# ULA.net
KiCad netlist of a schematic drawn in EAGLE
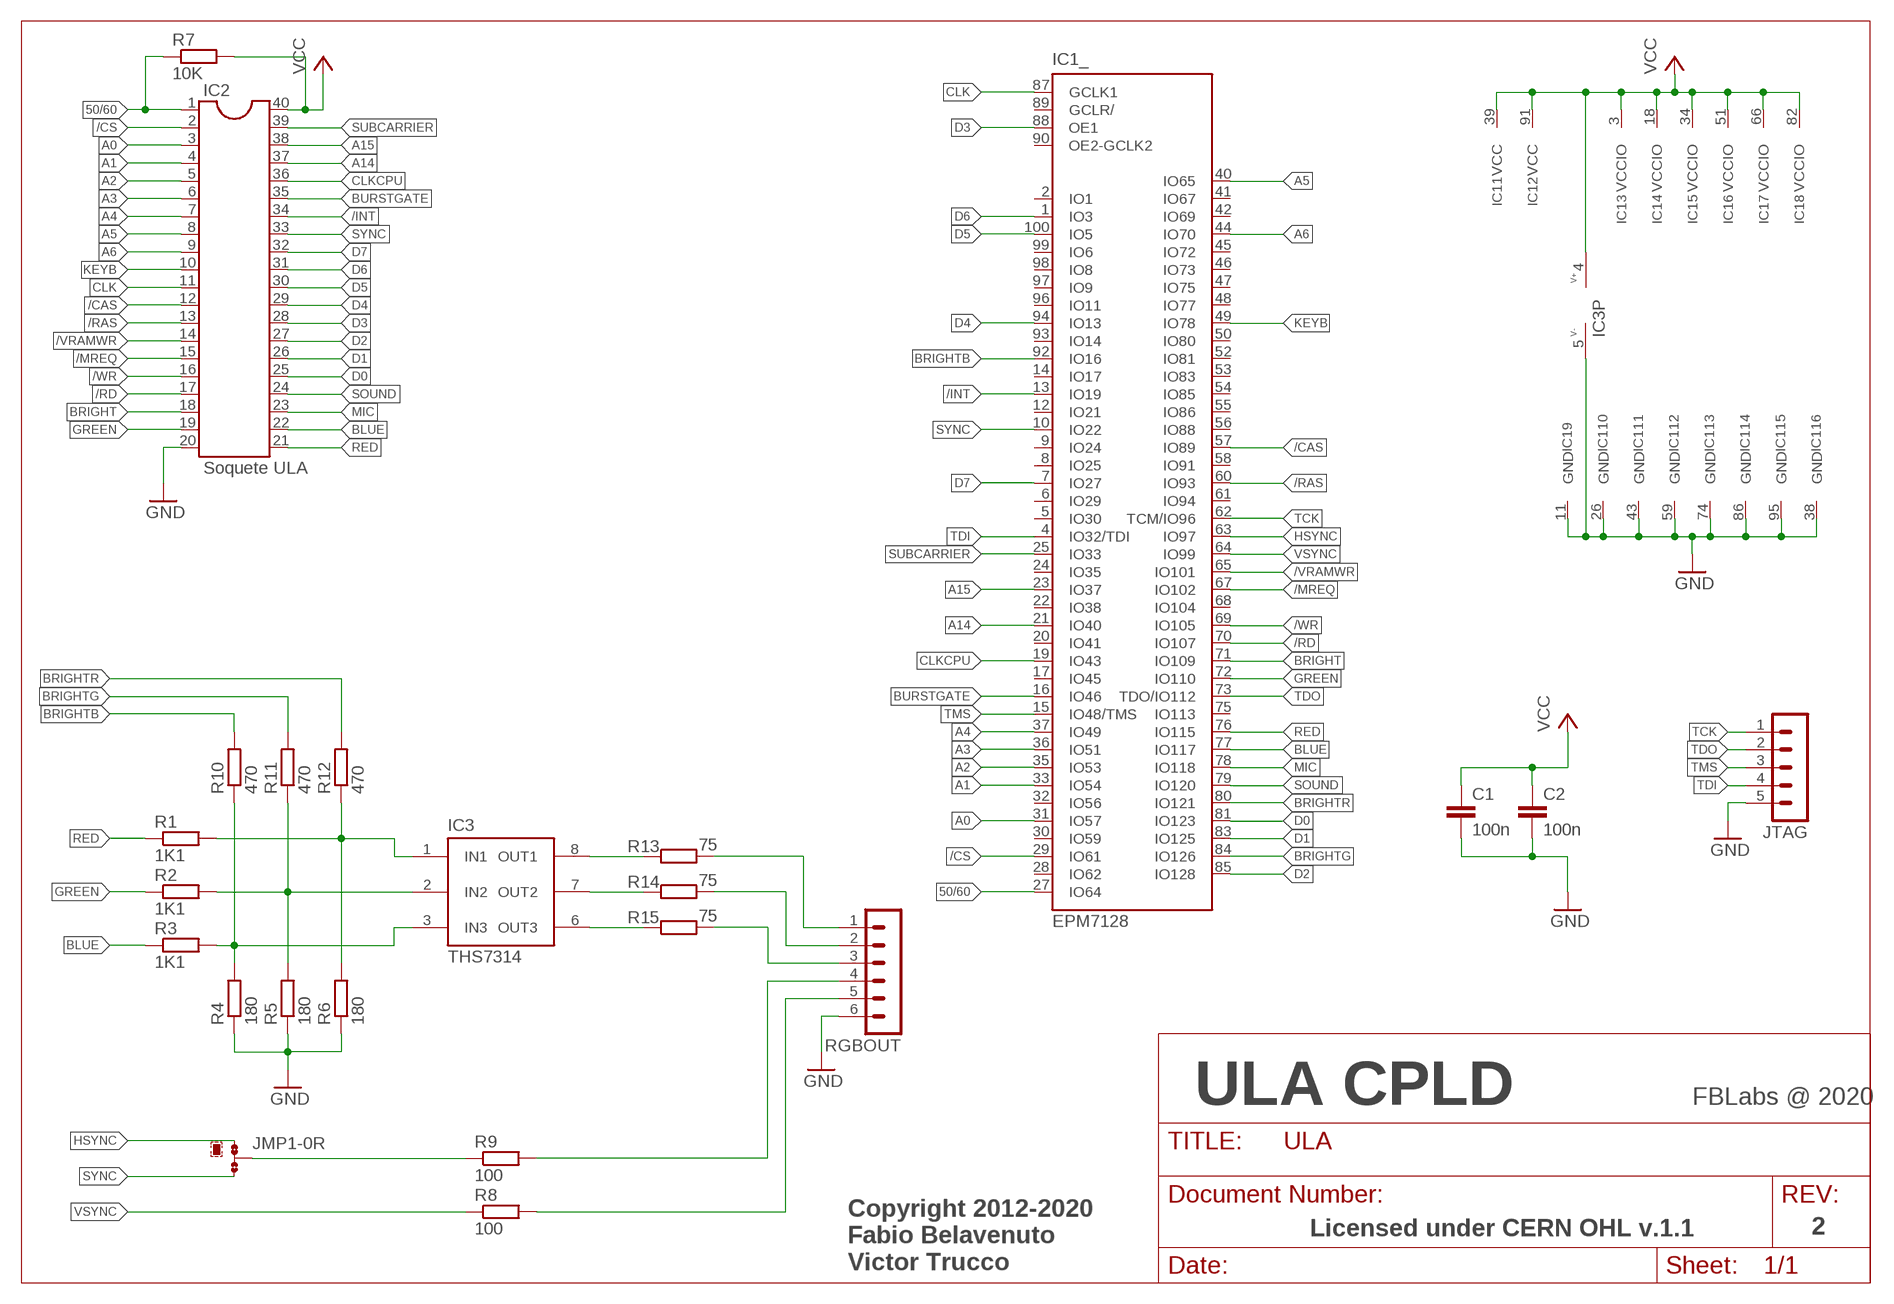
[diagram p0: schematic, sheet 1]

(export (version "E")
  (design (tool "Eeschema 10.0.6"))
  (components
    (comp (ref "C1")
      (value "100n")
      (footprint "eagle-import:C1206")
      (libsource (lib "eagle-import") (part "C-EUC1206"))
    )
    (comp (ref "C2")
      (value "100n")
      (footprint "eagle-import:C1206")
      (libsource (lib "eagle-import") (part "C-EUC1206"))
    )
    (comp (ref "IC1")
      (value "EPM7128")
      (footprint "eagle-import:TQFP100")
      (fields (field (name "MPN") "EPM7128STC100-7N"))
      (libsource (lib "eagle-import") (part "EPM7128-?100T"))
    )
    (comp (ref "IC2")
      (value "Soquete ULA")
      (footprint "eagle-import:DIL40")
      (libsource (lib "eagle-import") (part "DIL40"))
    )
    (comp (ref "IC3")
      (value "THS7314")
      (footprint "eagle-import:SOIC8")
      (libsource (lib "eagle-import") (part "THS7314"))
    )
    (comp (ref "JMP1")
      (value "0R-JUMPA")
      (footprint "eagle-import:A0R-JMP")
      (libsource (lib "eagle-import") (part "0R-JUMPA"))
    )
    (comp (ref "JTAG")
      (value "MA05-1")
      (footprint "eagle-import:MA05-1")
      (libsource (lib "eagle-import") (part "MA05-1"))
    )
    (comp (ref "R1")
      (value "1K1")
      (footprint "eagle-import:M0805")
      (libsource (lib "eagle-import") (part "R-EU_M0805"))
    )
    (comp (ref "R2")
      (value "1K1")
      (footprint "eagle-import:M0805")
      (libsource (lib "eagle-import") (part "R-EU_M0805"))
    )
    (comp (ref "R3")
      (value "1K1")
      (footprint "eagle-import:M0805")
      (libsource (lib "eagle-import") (part "R-EU_M0805"))
    )
    (comp (ref "R4")
      (value "180")
      (footprint "eagle-import:M0805")
      (libsource (lib "eagle-import") (part "R-EU_M0805"))
    )
    (comp (ref "R5")
      (value "180")
      (footprint "eagle-import:M0805")
      (libsource (lib "eagle-import") (part "R-EU_M0805"))
    )
    (comp (ref "R6")
      (value "180")
      (footprint "eagle-import:M0805")
      (libsource (lib "eagle-import") (part "R-EU_M0805"))
    )
    (comp (ref "R7")
      (value "10K")
      (footprint "eagle-import:M0805")
      (libsource (lib "eagle-import") (part "R-EU_M0805"))
    )
    (comp (ref "R8")
      (value "100")
      (footprint "eagle-import:M0805")
      (libsource (lib "eagle-import") (part "R-EU_M0805"))
    )
    (comp (ref "R9")
      (value "100")
      (footprint "eagle-import:M0805")
      (libsource (lib "eagle-import") (part "R-EU_M0805"))
    )
    (comp (ref "R10")
      (value "470")
      (footprint "eagle-import:M0805")
      (libsource (lib "eagle-import") (part "R-EU_M0805"))
    )
    (comp (ref "R11")
      (value "470")
      (footprint "eagle-import:M0805")
      (libsource (lib "eagle-import") (part "R-EU_M0805"))
    )
    (comp (ref "R12")
      (value "470")
      (footprint "eagle-import:M0805")
      (libsource (lib "eagle-import") (part "R-EU_M0805"))
    )
    (comp (ref "R13")
      (value "75")
      (footprint "eagle-import:M0805")
      (libsource (lib "eagle-import") (part "R-EU_M0805"))
    )
    (comp (ref "R14")
      (value "75")
      (footprint "eagle-import:M0805")
      (libsource (lib "eagle-import") (part "R-EU_M0805"))
    )
    (comp (ref "R15")
      (value "75")
      (footprint "eagle-import:M0805")
      (libsource (lib "eagle-import") (part "R-EU_M0805"))
    )
    (comp (ref "RGBOUT")
      (value "MA06-1")
      (footprint "eagle-import:MA06-1")
      (libsource (lib "eagle-import") (part "MA06-1"))
    )
  )
  (nets
    (net (code "1") (name "50{slash}60") (class "Default")
      (node (ref "IC1") (pin "27") (pinfunction "IO64_27") (pintype "bidirectional"))
      (node (ref "IC2") (pin "1") (pinfunction "1_1") (pintype "passive"))
      (node (ref "R7") (pin "1") (pinfunction "1_1") (pintype "passive"))
    )
    (net (code "2") (name "A0") (class "Default")
      (node (ref "IC1") (pin "31") (pinfunction "IO57_31") (pintype "bidirectional"))
      (node (ref "IC2") (pin "3") (pinfunction "3_3") (pintype "passive"))
    )
    (net (code "3") (name "A1") (class "Default")
      (node (ref "IC1") (pin "33") (pinfunction "IO54_33") (pintype "bidirectional"))
      (node (ref "IC2") (pin "4") (pinfunction "4_4") (pintype "passive"))
    )
    (net (code "4") (name "A2") (class "Default")
      (node (ref "IC1") (pin "35") (pinfunction "IO53_35") (pintype "bidirectional"))
      (node (ref "IC2") (pin "5") (pinfunction "5_5") (pintype "passive"))
    )
    (net (code "5") (name "A3") (class "Default")
      (node (ref "IC1") (pin "36") (pinfunction "IO51_36") (pintype "bidirectional"))
      (node (ref "IC2") (pin "6") (pinfunction "6_6") (pintype "passive"))
    )
    (net (code "6") (name "A4") (class "Default")
      (node (ref "IC1") (pin "37") (pinfunction "IO49_37") (pintype "bidirectional"))
      (node (ref "IC2") (pin "7") (pinfunction "7_7") (pintype "passive"))
    )
    (net (code "7") (name "A5") (class "Default")
      (node (ref "IC1") (pin "40") (pinfunction "IO65_40") (pintype "bidirectional"))
      (node (ref "IC2") (pin "8") (pinfunction "8_8") (pintype "passive"))
    )
    (net (code "8") (name "A6") (class "Default")
      (node (ref "IC1") (pin "44") (pinfunction "IO70_44") (pintype "bidirectional"))
      (node (ref "IC2") (pin "9") (pinfunction "9_9") (pintype "passive"))
    )
    (net (code "9") (name "A14") (class "Default")
      (node (ref "IC1") (pin "21") (pinfunction "IO40_21") (pintype "bidirectional"))
      (node (ref "IC2") (pin "37") (pinfunction "37_37") (pintype "passive"))
    )
    (net (code "10") (name "A15") (class "Default")
      (node (ref "IC1") (pin "23") (pinfunction "IO37_23") (pintype "bidirectional"))
      (node (ref "IC2") (pin "38") (pinfunction "38_38") (pintype "passive"))
    )
    (net (code "11") (name "BLUE") (class "Default")
      (node (ref "IC1") (pin "77") (pinfunction "IO117_77") (pintype "bidirectional"))
      (node (ref "IC2") (pin "22") (pinfunction "22_22") (pintype "passive"))
      (node (ref "R3") (pin "1") (pinfunction "1_1") (pintype "passive"))
    )
    (net (code "12") (name "BRIGHT") (class "Default")
      (node (ref "IC1") (pin "71") (pinfunction "IO109_71") (pintype "bidirectional"))
      (node (ref "IC2") (pin "18") (pinfunction "18_18") (pintype "passive"))
    )
    (net (code "13") (name "BRIGHTB") (class "Default")
      (node (ref "IC1") (pin "92") (pinfunction "IO16_92") (pintype "bidirectional"))
      (node (ref "R10") (pin "2") (pinfunction "2_2") (pintype "passive"))
    )
    (net (code "14") (name "BRIGHTG") (class "Default")
      (node (ref "IC1") (pin "84") (pinfunction "IO126_84") (pintype "bidirectional"))
      (node (ref "R11") (pin "2") (pinfunction "2_2") (pintype "passive"))
    )
    (net (code "15") (name "BRIGHTR") (class "Default")
      (node (ref "IC1") (pin "80") (pinfunction "IO121_80") (pintype "bidirectional"))
      (node (ref "R12") (pin "2") (pinfunction "2_2") (pintype "passive"))
    )
    (net (code "16") (name "BURSTGATE") (class "Default")
      (node (ref "IC1") (pin "16") (pinfunction "IO46_16") (pintype "bidirectional"))
      (node (ref "IC2") (pin "35") (pinfunction "35_35") (pintype "passive"))
    )
    (net (code "17") (name "CLK") (class "Default")
      (node (ref "IC1") (pin "87") (pinfunction "GCLK1_87") (pintype "input"))
      (node (ref "IC2") (pin "11") (pinfunction "11_11") (pintype "passive"))
    )
    (net (code "18") (name "CLKCPU") (class "Default")
      (node (ref "IC1") (pin "19") (pinfunction "IO43_19") (pintype "bidirectional"))
      (node (ref "IC2") (pin "36") (pinfunction "36_36") (pintype "passive"))
    )
    (net (code "19") (name "D0") (class "Default")
      (node (ref "IC1") (pin "81") (pinfunction "IO123_81") (pintype "bidirectional"))
      (node (ref "IC2") (pin "25") (pinfunction "25_25") (pintype "passive"))
    )
    (net (code "20") (name "D1") (class "Default")
      (node (ref "IC1") (pin "83") (pinfunction "IO125_83") (pintype "bidirectional"))
      (node (ref "IC2") (pin "26") (pinfunction "26_26") (pintype "passive"))
    )
    (net (code "21") (name "D2") (class "Default")
      (node (ref "IC1") (pin "85") (pinfunction "IO128_85") (pintype "bidirectional"))
      (node (ref "IC2") (pin "27") (pinfunction "27_27") (pintype "passive"))
    )
    (net (code "22") (name "D3") (class "Default")
      (node (ref "IC1") (pin "88") (pinfunction "OE1_88") (pintype "input"))
      (node (ref "IC2") (pin "28") (pinfunction "28_28") (pintype "passive"))
    )
    (net (code "23") (name "D4") (class "Default")
      (node (ref "IC1") (pin "94") (pinfunction "IO13_94") (pintype "bidirectional"))
      (node (ref "IC2") (pin "29") (pinfunction "29_29") (pintype "passive"))
    )
    (net (code "24") (name "D5") (class "Default")
      (node (ref "IC1") (pin "100") (pinfunction "IO5_100") (pintype "bidirectional"))
      (node (ref "IC2") (pin "30") (pinfunction "30_30") (pintype "passive"))
    )
    (net (code "25") (name "D6") (class "Default")
      (node (ref "IC1") (pin "1") (pinfunction "IO3_1") (pintype "bidirectional"))
      (node (ref "IC2") (pin "31") (pinfunction "31_31") (pintype "passive"))
    )
    (net (code "26") (name "D7") (class "Default")
      (node (ref "IC1") (pin "7") (pinfunction "IO27_7") (pintype "bidirectional"))
      (node (ref "IC2") (pin "32") (pinfunction "32_32") (pintype "passive"))
    )
    (net (code "27") (name "GND") (class "Default")
      (node (ref "C1") (pin "2") (pinfunction "2_2") (pintype "passive"))
      (node (ref "C2") (pin "2") (pinfunction "2_2") (pintype "passive"))
      (node (ref "IC1") (pin "11") (pinfunction "GND_11") (pintype "power_in"))
      (node (ref "IC1") (pin "26") (pinfunction "GND_26") (pintype "power_in"))
      (node (ref "IC1") (pin "38") (pinfunction "GND_38") (pintype "power_in"))
      (node (ref "IC1") (pin "43") (pinfunction "GND_43") (pintype "power_in"))
      (node (ref "IC1") (pin "59") (pinfunction "GND_59") (pintype "power_in"))
      (node (ref "IC1") (pin "74") (pinfunction "GND_74") (pintype "power_in"))
      (node (ref "IC1") (pin "86") (pinfunction "GND_86") (pintype "power_in"))
      (node (ref "IC1") (pin "95") (pinfunction "GND_95") (pintype "power_in"))
      (node (ref "IC2") (pin "20") (pinfunction "20_20") (pintype "passive"))
      (node (ref "IC3") (pin "5") (pinfunction "V-_5") (pintype "power_in"))
      (node (ref "JTAG") (pin "5") (pinfunction "5_5") (pintype "passive"))
      (node (ref "R4") (pin "1") (pinfunction "1_1") (pintype "passive"))
      (node (ref "R5") (pin "1") (pinfunction "1_1") (pintype "passive"))
      (node (ref "R6") (pin "1") (pinfunction "1_1") (pintype "passive"))
      (node (ref "RGBOUT") (pin "6") (pinfunction "6_6") (pintype "passive"))
    )
    (net (code "28") (name "GREEN") (class "Default")
      (node (ref "IC1") (pin "72") (pinfunction "IO110_72") (pintype "bidirectional"))
      (node (ref "IC2") (pin "19") (pinfunction "19_19") (pintype "passive"))
      (node (ref "R2") (pin "1") (pinfunction "1_1") (pintype "passive"))
    )
    (net (code "29") (name "HSYNC") (class "Default")
      (node (ref "IC1") (pin "63") (pinfunction "IO97_63") (pintype "bidirectional"))
      (node (ref "JMP1") (pin "1") (pinfunction "1_1") (pintype "passive"))
    )
    (net (code "30") (name "KEYB") (class "Default")
      (node (ref "IC1") (pin "49") (pinfunction "IO78_49") (pintype "bidirectional"))
      (node (ref "IC2") (pin "10") (pinfunction "10_10") (pintype "passive"))
    )
    (net (code "31") (name "MIC") (class "Default")
      (node (ref "IC1") (pin "78") (pinfunction "IO118_78") (pintype "bidirectional"))
      (node (ref "IC2") (pin "23") (pinfunction "23_23") (pintype "passive"))
    )
    (net (code "32") (name "Net-(IC3A-IN1)") (class "Default")
      (node (ref "IC3") (pin "1") (pinfunction "IN1_1") (pintype "input"))
      (node (ref "R1") (pin "2") (pinfunction "2_2") (pintype "passive"))
      (node (ref "R12") (pin "1") (pinfunction "1_1") (pintype "passive"))
      (node (ref "R6") (pin "2") (pinfunction "2_2") (pintype "passive"))
    )
    (net (code "33") (name "Net-(IC3A-IN2)") (class "Default")
      (node (ref "IC3") (pin "2") (pinfunction "IN2_2") (pintype "input"))
      (node (ref "R11") (pin "1") (pinfunction "1_1") (pintype "passive"))
      (node (ref "R2") (pin "2") (pinfunction "2_2") (pintype "passive"))
      (node (ref "R5") (pin "2") (pinfunction "2_2") (pintype "passive"))
    )
    (net (code "34") (name "Net-(IC3A-IN3)") (class "Default")
      (node (ref "IC3") (pin "3") (pinfunction "IN3_3") (pintype "input"))
      (node (ref "R10") (pin "1") (pinfunction "1_1") (pintype "passive"))
      (node (ref "R3") (pin "2") (pinfunction "2_2") (pintype "passive"))
      (node (ref "R4") (pin "2") (pinfunction "2_2") (pintype "passive"))
    )
    (net (code "35") (name "Net-(IC3A-OUT1)") (class "Default")
      (node (ref "IC3") (pin "8") (pinfunction "OUT1_8") (pintype "output"))
      (node (ref "R13") (pin "1") (pinfunction "1_1") (pintype "passive"))
    )
    (net (code "36") (name "Net-(IC3A-OUT2)") (class "Default")
      (node (ref "IC3") (pin "7") (pinfunction "OUT2_7") (pintype "output"))
      (node (ref "R14") (pin "1") (pinfunction "1_1") (pintype "passive"))
    )
    (net (code "37") (name "Net-(IC3A-OUT3)") (class "Default")
      (node (ref "IC3") (pin "6") (pinfunction "OUT3_6") (pintype "output"))
      (node (ref "R15") (pin "1") (pinfunction "1_1") (pintype "passive"))
    )
    (net (code "38") (name "Net-(JMP1-Pad2)") (class "Default")
      (node (ref "JMP1") (pin "2") (pinfunction "2_2") (pintype "passive"))
      (node (ref "R9") (pin "1") (pinfunction "1_1") (pintype "passive"))
    )
    (net (code "39") (name "Net-(R8-Pad2)") (class "Default")
      (node (ref "R8") (pin "2") (pinfunction "2_2") (pintype "passive"))
      (node (ref "RGBOUT") (pin "5") (pinfunction "5_5") (pintype "passive"))
    )
    (net (code "40") (name "Net-(R9-Pad2)") (class "Default")
      (node (ref "R9") (pin "2") (pinfunction "2_2") (pintype "passive"))
      (node (ref "RGBOUT") (pin "4") (pinfunction "4_4") (pintype "passive"))
    )
    (net (code "41") (name "Net-(R13-Pad2)") (class "Default")
      (node (ref "R13") (pin "2") (pinfunction "2_2") (pintype "passive"))
      (node (ref "RGBOUT") (pin "1") (pinfunction "1_1") (pintype "passive"))
    )
    (net (code "42") (name "Net-(R14-Pad2)") (class "Default")
      (node (ref "R14") (pin "2") (pinfunction "2_2") (pintype "passive"))
      (node (ref "RGBOUT") (pin "2") (pinfunction "2_2") (pintype "passive"))
    )
    (net (code "43") (name "Net-(R15-Pad2)") (class "Default")
      (node (ref "R15") (pin "2") (pinfunction "2_2") (pintype "passive"))
      (node (ref "RGBOUT") (pin "3") (pinfunction "3_3") (pintype "passive"))
    )
    (net (code "44") (name "RED") (class "Default")
      (node (ref "IC1") (pin "76") (pinfunction "IO115_76") (pintype "bidirectional"))
      (node (ref "IC2") (pin "21") (pinfunction "21_21") (pintype "passive"))
      (node (ref "R1") (pin "1") (pinfunction "1_1") (pintype "passive"))
    )
    (net (code "45") (name "SOUND") (class "Default")
      (node (ref "IC1") (pin "79") (pinfunction "IO120_79") (pintype "bidirectional"))
      (node (ref "IC2") (pin "24") (pinfunction "24_24") (pintype "passive"))
    )
    (net (code "46") (name "SUBCARRIER") (class "Default")
      (node (ref "IC1") (pin "25") (pinfunction "IO33_25") (pintype "bidirectional"))
      (node (ref "IC2") (pin "39") (pinfunction "39_39") (pintype "passive"))
    )
    (net (code "47") (name "SYNC") (class "Default")
      (node (ref "IC1") (pin "10") (pinfunction "IO22_10") (pintype "bidirectional"))
      (node (ref "IC2") (pin "33") (pinfunction "33_33") (pintype "passive"))
      (node (ref "JMP1") (pin "3") (pinfunction "3_3") (pintype "passive"))
    )
    (net (code "48") (name "TCK") (class "Default")
      (node (ref "IC1") (pin "62") (pinfunction "TCM/IO96_62") (pintype "bidirectional"))
      (node (ref "JTAG") (pin "1") (pinfunction "1_1") (pintype "passive"))
    )
    (net (code "49") (name "TDI") (class "Default")
      (node (ref "IC1") (pin "4") (pinfunction "IO32/TDI_4") (pintype "bidirectional"))
      (node (ref "JTAG") (pin "4") (pinfunction "4_4") (pintype "passive"))
    )
    (net (code "50") (name "TDO") (class "Default")
      (node (ref "IC1") (pin "73") (pinfunction "TDO/IO112_73") (pintype "bidirectional"))
      (node (ref "JTAG") (pin "2") (pinfunction "2_2") (pintype "passive"))
    )
    (net (code "51") (name "TMS") (class "Default")
      (node (ref "IC1") (pin "15") (pinfunction "IO48/TMS_15") (pintype "bidirectional"))
      (node (ref "JTAG") (pin "3") (pinfunction "3_3") (pintype "passive"))
    )
    (net (code "52") (name "VCC") (class "Default")
      (node (ref "C1") (pin "1") (pinfunction "1_1") (pintype "passive"))
      (node (ref "C2") (pin "1") (pinfunction "1_1") (pintype "passive"))
      (node (ref "IC1") (pin "18") (pinfunction "VCCIO_18") (pintype "power_in"))
      (node (ref "IC1") (pin "3") (pinfunction "VCCIO_3") (pintype "power_in"))
      (node (ref "IC1") (pin "34") (pinfunction "VCCIO_34") (pintype "power_in"))
      (node (ref "IC1") (pin "39") (pinfunction "VCC_39") (pintype "power_in"))
      (node (ref "IC1") (pin "51") (pinfunction "VCCIO_51") (pintype "power_in"))
      (node (ref "IC1") (pin "66") (pinfunction "VCCIO_66") (pintype "power_in"))
      (node (ref "IC1") (pin "82") (pinfunction "VCCIO_82") (pintype "power_in"))
      (node (ref "IC1") (pin "91") (pinfunction "VCC_91") (pintype "power_in"))
      (node (ref "IC2") (pin "40") (pinfunction "40_40") (pintype "passive"))
      (node (ref "IC3") (pin "4") (pinfunction "V+_4") (pintype "power_in"))
      (node (ref "R7") (pin "2") (pinfunction "2_2") (pintype "passive"))
    )
    (net (code "53") (name "VSYNC") (class "Default")
      (node (ref "IC1") (pin "64") (pinfunction "IO99_64") (pintype "bidirectional"))
      (node (ref "R8") (pin "1") (pinfunction "1_1") (pintype "passive"))
    )
    (net (code "54") (name "unconnected-(IC1Q-GCLR{slash}-Pad89)") (class "Default")
      (node (ref "IC1") (pin "89") (pinfunction "GCLR/_89") (pintype "input"))
    )
    (net (code "55") (name "unconnected-(IC1Q-IO1-Pad2)") (class "Default")
      (node (ref "IC1") (pin "2") (pinfunction "IO1_2") (pintype "bidirectional"))
    )
    (net (code "56") (name "unconnected-(IC1Q-IO6-Pad99)") (class "Default")
      (node (ref "IC1") (pin "99") (pinfunction "IO6_99") (pintype "bidirectional"))
    )
    (net (code "57") (name "unconnected-(IC1Q-IO8-Pad98)") (class "Default")
      (node (ref "IC1") (pin "98") (pinfunction "IO8_98") (pintype "bidirectional"))
    )
    (net (code "58") (name "unconnected-(IC1Q-IO9-Pad97)") (class "Default")
      (node (ref "IC1") (pin "97") (pinfunction "IO9_97") (pintype "bidirectional"))
    )
    (net (code "59") (name "unconnected-(IC1Q-IO11-Pad96)") (class "Default")
      (node (ref "IC1") (pin "96") (pinfunction "IO11_96") (pintype "bidirectional"))
    )
    (net (code "60") (name "unconnected-(IC1Q-IO14-Pad93)") (class "Default")
      (node (ref "IC1") (pin "93") (pinfunction "IO14_93") (pintype "bidirectional"))
    )
    (net (code "61") (name "unconnected-(IC1Q-IO17-Pad14)") (class "Default")
      (node (ref "IC1") (pin "14") (pinfunction "IO17_14") (pintype "bidirectional"))
    )
    (net (code "62") (name "unconnected-(IC1Q-IO21-Pad12)") (class "Default")
      (node (ref "IC1") (pin "12") (pinfunction "IO21_12") (pintype "bidirectional"))
    )
    (net (code "63") (name "unconnected-(IC1Q-IO24-Pad9)") (class "Default")
      (node (ref "IC1") (pin "9") (pinfunction "IO24_9") (pintype "bidirectional"))
    )
    (net (code "64") (name "unconnected-(IC1Q-IO25-Pad8)") (class "Default")
      (node (ref "IC1") (pin "8") (pinfunction "IO25_8") (pintype "bidirectional"))
    )
    (net (code "65") (name "unconnected-(IC1Q-IO29-Pad6)") (class "Default")
      (node (ref "IC1") (pin "6") (pinfunction "IO29_6") (pintype "bidirectional"))
    )
    (net (code "66") (name "unconnected-(IC1Q-IO30-Pad5)") (class "Default")
      (node (ref "IC1") (pin "5") (pinfunction "IO30_5") (pintype "bidirectional"))
    )
    (net (code "67") (name "unconnected-(IC1Q-IO35-Pad24)") (class "Default")
      (node (ref "IC1") (pin "24") (pinfunction "IO35_24") (pintype "bidirectional"))
    )
    (net (code "68") (name "unconnected-(IC1Q-IO38-Pad22)") (class "Default")
      (node (ref "IC1") (pin "22") (pinfunction "IO38_22") (pintype "bidirectional"))
    )
    (net (code "69") (name "unconnected-(IC1Q-IO41-Pad20)") (class "Default")
      (node (ref "IC1") (pin "20") (pinfunction "IO41_20") (pintype "bidirectional"))
    )
    (net (code "70") (name "unconnected-(IC1Q-IO45-Pad17)") (class "Default")
      (node (ref "IC1") (pin "17") (pinfunction "IO45_17") (pintype "bidirectional"))
    )
    (net (code "71") (name "unconnected-(IC1Q-IO56-Pad32)") (class "Default")
      (node (ref "IC1") (pin "32") (pinfunction "IO56_32") (pintype "bidirectional"))
    )
    (net (code "72") (name "unconnected-(IC1Q-IO59-Pad30)") (class "Default")
      (node (ref "IC1") (pin "30") (pinfunction "IO59_30") (pintype "bidirectional"))
    )
    (net (code "73") (name "unconnected-(IC1Q-IO62-Pad28)") (class "Default")
      (node (ref "IC1") (pin "28") (pinfunction "IO62_28") (pintype "bidirectional"))
    )
    (net (code "74") (name "unconnected-(IC1Q-IO67-Pad41)") (class "Default")
      (node (ref "IC1") (pin "41") (pinfunction "IO67_41") (pintype "bidirectional"))
    )
    (net (code "75") (name "unconnected-(IC1Q-IO69-Pad42)") (class "Default")
      (node (ref "IC1") (pin "42") (pinfunction "IO69_42") (pintype "bidirectional"))
    )
    (net (code "76") (name "unconnected-(IC1Q-IO72-Pad45)") (class "Default")
      (node (ref "IC1") (pin "45") (pinfunction "IO72_45") (pintype "bidirectional"))
    )
    (net (code "77") (name "unconnected-(IC1Q-IO73-Pad46)") (class "Default")
      (node (ref "IC1") (pin "46") (pinfunction "IO73_46") (pintype "bidirectional"))
    )
    (net (code "78") (name "unconnected-(IC1Q-IO75-Pad47)") (class "Default")
      (node (ref "IC1") (pin "47") (pinfunction "IO75_47") (pintype "bidirectional"))
    )
    (net (code "79") (name "unconnected-(IC1Q-IO77-Pad48)") (class "Default")
      (node (ref "IC1") (pin "48") (pinfunction "IO77_48") (pintype "bidirectional"))
    )
    (net (code "80") (name "unconnected-(IC1Q-IO80-Pad50)") (class "Default")
      (node (ref "IC1") (pin "50") (pinfunction "IO80_50") (pintype "bidirectional"))
    )
    (net (code "81") (name "unconnected-(IC1Q-IO81-Pad52)") (class "Default")
      (node (ref "IC1") (pin "52") (pinfunction "IO81_52") (pintype "bidirectional"))
    )
    (net (code "82") (name "unconnected-(IC1Q-IO83-Pad53)") (class "Default")
      (node (ref "IC1") (pin "53") (pinfunction "IO83_53") (pintype "bidirectional"))
    )
    (net (code "83") (name "unconnected-(IC1Q-IO85-Pad54)") (class "Default")
      (node (ref "IC1") (pin "54") (pinfunction "IO85_54") (pintype "bidirectional"))
    )
    (net (code "84") (name "unconnected-(IC1Q-IO86-Pad55)") (class "Default")
      (node (ref "IC1") (pin "55") (pinfunction "IO86_55") (pintype "bidirectional"))
    )
    (net (code "85") (name "unconnected-(IC1Q-IO88-Pad56)") (class "Default")
      (node (ref "IC1") (pin "56") (pinfunction "IO88_56") (pintype "bidirectional"))
    )
    (net (code "86") (name "unconnected-(IC1Q-IO91-Pad58)") (class "Default")
      (node (ref "IC1") (pin "58") (pinfunction "IO91_58") (pintype "bidirectional"))
    )
    (net (code "87") (name "unconnected-(IC1Q-IO94-Pad61)") (class "Default")
      (node (ref "IC1") (pin "61") (pinfunction "IO94_61") (pintype "bidirectional"))
    )
    (net (code "88") (name "unconnected-(IC1Q-IO104-Pad68)") (class "Default")
      (node (ref "IC1") (pin "68") (pinfunction "IO104_68") (pintype "bidirectional"))
    )
    (net (code "89") (name "unconnected-(IC1Q-IO113-Pad75)") (class "Default")
      (node (ref "IC1") (pin "75") (pinfunction "IO113_75") (pintype "bidirectional"))
    )
    (net (code "90") (name "unconnected-(IC1Q-OE2-GCLK2-Pad90)") (class "Default")
      (node (ref "IC1") (pin "90") (pinfunction "OE2-GCLK2_90") (pintype "input"))
    )
    (net (code "91") (name "{slash}CAS") (class "Default")
      (node (ref "IC1") (pin "57") (pinfunction "IO89_57") (pintype "bidirectional"))
      (node (ref "IC2") (pin "12") (pinfunction "12_12") (pintype "passive"))
    )
    (net (code "92") (name "{slash}CS") (class "Default")
      (node (ref "IC1") (pin "29") (pinfunction "IO61_29") (pintype "bidirectional"))
      (node (ref "IC2") (pin "2") (pinfunction "2_2") (pintype "passive"))
    )
    (net (code "93") (name "{slash}INT") (class "Default")
      (node (ref "IC1") (pin "13") (pinfunction "IO19_13") (pintype "bidirectional"))
      (node (ref "IC2") (pin "34") (pinfunction "34_34") (pintype "passive"))
    )
    (net (code "94") (name "{slash}MREQ") (class "Default")
      (node (ref "IC1") (pin "67") (pinfunction "IO102_67") (pintype "bidirectional"))
      (node (ref "IC2") (pin "15") (pinfunction "15_15") (pintype "passive"))
    )
    (net (code "95") (name "{slash}RAS") (class "Default")
      (node (ref "IC1") (pin "60") (pinfunction "IO93_60") (pintype "bidirectional"))
      (node (ref "IC2") (pin "13") (pinfunction "13_13") (pintype "passive"))
    )
    (net (code "96") (name "{slash}RD") (class "Default")
      (node (ref "IC1") (pin "70") (pinfunction "IO107_70") (pintype "bidirectional"))
      (node (ref "IC2") (pin "17") (pinfunction "17_17") (pintype "passive"))
    )
    (net (code "97") (name "{slash}VRAMWR") (class "Default")
      (node (ref "IC1") (pin "65") (pinfunction "IO101_65") (pintype "bidirectional"))
      (node (ref "IC2") (pin "14") (pinfunction "14_14") (pintype "passive"))
    )
    (net (code "98") (name "{slash}WR") (class "Default")
      (node (ref "IC1") (pin "69") (pinfunction "IO105_69") (pintype "bidirectional"))
      (node (ref "IC2") (pin "16") (pinfunction "16_16") (pintype "passive"))
    )
  )
)
